# relay.net
KiCad netlist of a schematic drawn in Altium Designer
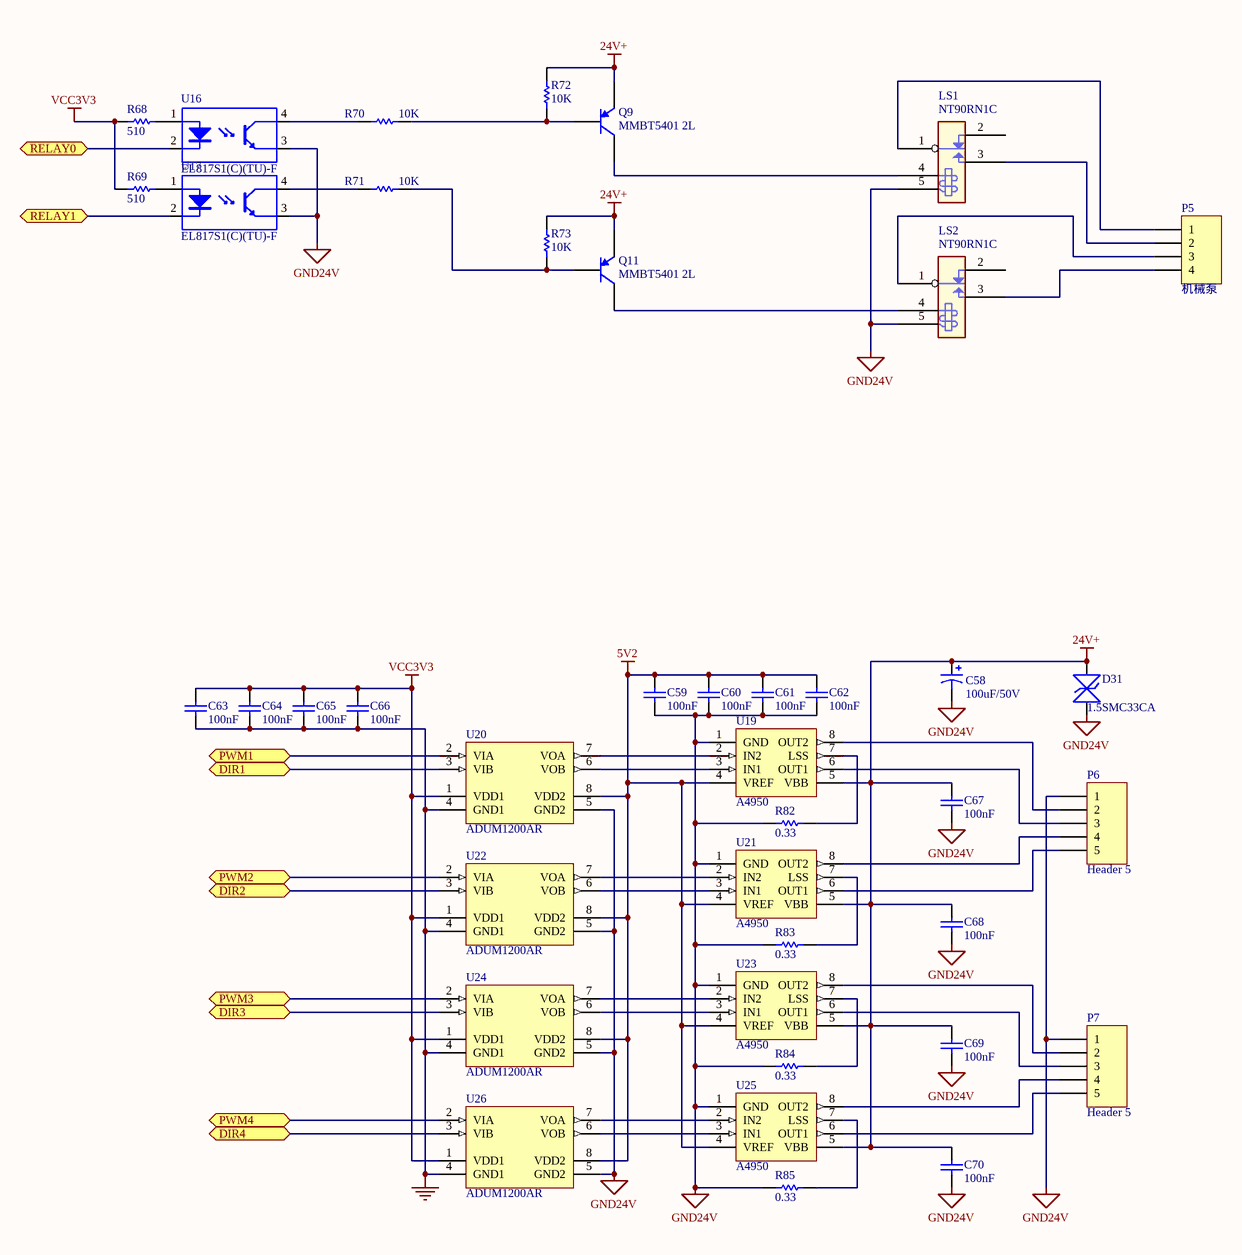
[diagram p0: relay.SchDoc]

(export (version "E")
  (design (tool "Eeschema 10.0.6"))
  (components
    (comp (ref "C58")
      (value "100uF/50V")
      (footprint "CD1.5/3.2")
      (description "Polarized Capacitor (Radial)")
      (fields (field (name "PUBLISHER") "Altium Limited"))
      (libsource (lib "Miscellaneous Devices") (part "Cap Pol1"))
    )
    (comp (ref "C59")
      (value "100nF")
      (footprint "0805_C")
      (description "贴片电容")
      (libsource (lib "Miscellaneous Devices LC") (part "0805 100nF(104) 10% 50V"))
    )
    (comp (ref "C60")
      (value "100nF")
      (footprint "0805_C")
      (description "贴片电容")
      (libsource (lib "Miscellaneous Devices LC") (part "0805 100nF(104) 10% 50V"))
    )
    (comp (ref "C61")
      (value "100nF")
      (footprint "0805_C")
      (description "贴片电容")
      (libsource (lib "Miscellaneous Devices LC") (part "0805 100nF(104) 10% 50V"))
    )
    (comp (ref "C62")
      (value "100nF")
      (footprint "0805_C")
      (description "贴片电容")
      (libsource (lib "Miscellaneous Devices LC") (part "0805 100nF(104) 10% 50V"))
    )
    (comp (ref "C63")
      (value "100nF")
      (footprint "0805_C")
      (description "贴片电容")
      (libsource (lib "Miscellaneous Devices LC") (part "0805 100nF(104) 10% 50V"))
    )
    (comp (ref "C64")
      (value "100nF")
      (footprint "0805_C")
      (description "贴片电容")
      (libsource (lib "Miscellaneous Devices LC") (part "0805 100nF(104) 10% 50V"))
    )
    (comp (ref "C65")
      (value "100nF")
      (footprint "0805_C")
      (description "贴片电容")
      (libsource (lib "Miscellaneous Devices LC") (part "0805 100nF(104) 10% 50V"))
    )
    (comp (ref "C66")
      (value "100nF")
      (footprint "0805_C")
      (description "贴片电容")
      (libsource (lib "Miscellaneous Devices LC") (part "0805 100nF(104) 10% 50V"))
    )
    (comp (ref "C67")
      (value "100nF")
      (footprint "0805_C")
      (description "贴片电容")
      (libsource (lib "Miscellaneous Devices LC") (part "0805 100nF(104) 10% 50V"))
    )
    (comp (ref "C68")
      (value "100nF")
      (footprint "0805_C")
      (description "贴片电容")
      (libsource (lib "Miscellaneous Devices LC") (part "0805 100nF(104) 10% 50V"))
    )
    (comp (ref "C69")
      (value "100nF")
      (footprint "0805_C")
      (description "贴片电容")
      (libsource (lib "Miscellaneous Devices LC") (part "0805 100nF(104) 10% 50V"))
    )
    (comp (ref "C70")
      (value "100nF")
      (footprint "0805_C")
      (description "贴片电容")
      (libsource (lib "Miscellaneous Devices LC") (part "0805 100nF(104) 10% 50V"))
    )
    (comp (ref "D31") (value "1.5SMC33CA") (footprint "SMC(DO-214AB)_S1") (libsource (lib "IC") (part "TVS")))
    (comp (ref "LS1") (value "NT90RN1C") (libsource (lib "Devices") (part "NT90RN1C")))
    (comp (ref "LS2") (value "NT90RN1C") (libsource (lib "Devices") (part "NT90RN1C")))
    (comp (ref "P5")
      (value "机械泵")
      (footprint "MSTBV 2.5/4-G-5.08")
      (description "Header, 4-Pin, Right Angle")
      (fields (field (name "PUBLISHER") "Altium Limited"))
      (libsource (lib "Miscellaneous Connectors") (part "Header 4H"))
    )
    (comp (ref "P6")
      (value "Header 5")
      (footprint "MC1.5/5-ST-3.81")
      (description "Header, 5-Pin")
      (fields (field (name "PUBLISHER") "Altium Limited"))
      (libsource (lib "Miscellaneous Connectors") (part "Header 5"))
    )
    (comp (ref "P7")
      (value "Header 5")
      (footprint "MC1.5/5-ST-3.81")
      (description "Header, 5-Pin")
      (fields (field (name "PUBLISHER") "Altium Limited"))
      (libsource (lib "Miscellaneous Connectors") (part "Header 5"))
    )
    (comp (ref "Q9")
      (value "MMBT5401 2L")
      (footprint "SOT-23(SOT-23-3)")
      (description "三极管")
      (libsource (lib "Miscellaneous Devices LC") (part "SOT-23 MMBT5401 2L"))
    )
    (comp (ref "Q11")
      (value "MMBT5401 2L")
      (footprint "SOT-23(SOT-23-3)")
      (description "三极管")
      (libsource (lib "Miscellaneous Devices LC") (part "SOT-23 MMBT5401 2L"))
    )
    (comp (ref "R68")
      (value "510")
      (footprint "0805_R")
      (description "Resistor")
      (fields (field (name "PUBLISHER") "Altium Limited"))
      (libsource (lib "Miscellaneous Devices") (part "Res1"))
    )
    (comp (ref "R69")
      (value "510")
      (footprint "0805_R")
      (description "Resistor")
      (fields (field (name "PUBLISHER") "Altium Limited"))
      (libsource (lib "Miscellaneous Devices") (part "Res1"))
    )
    (comp (ref "R70")
      (value "10K")
      (footprint "0805_R")
      (description "Resistor")
      (fields (field (name "PUBLISHER") "Altium Limited"))
      (libsource (lib "Miscellaneous Devices") (part "Res1"))
    )
    (comp (ref "R71")
      (value "10K")
      (footprint "0805_R")
      (description "Resistor")
      (fields (field (name "PUBLISHER") "Altium Limited"))
      (libsource (lib "Miscellaneous Devices") (part "Res1"))
    )
    (comp (ref "R72")
      (value "10K")
      (footprint "0805_R")
      (description "Resistor")
      (fields (field (name "PUBLISHER") "Altium Limited"))
      (libsource (lib "Miscellaneous Devices") (part "Res1"))
    )
    (comp (ref "R73")
      (value "10K")
      (footprint "0805_R")
      (description "Resistor")
      (fields (field (name "PUBLISHER") "Altium Limited"))
      (libsource (lib "Miscellaneous Devices") (part "Res1"))
    )
    (comp (ref "R82")
      (value "0.33")
      (footprint "R2512")
      (description "Resistor")
      (fields (field (name "PUBLISHER") "Altium Limited"))
      (libsource (lib "Miscellaneous Devices") (part "Res1"))
    )
    (comp (ref "R83")
      (value "0.33")
      (footprint "R2512")
      (description "Resistor")
      (fields (field (name "PUBLISHER") "Altium Limited"))
      (libsource (lib "Miscellaneous Devices") (part "Res1"))
    )
    (comp (ref "R84")
      (value "0.33")
      (footprint "R2512")
      (description "Resistor")
      (fields (field (name "PUBLISHER") "Altium Limited"))
      (libsource (lib "Miscellaneous Devices") (part "Res1"))
    )
    (comp (ref "R85")
      (value "0.33")
      (footprint "R2512")
      (description "Resistor")
      (fields (field (name "PUBLISHER") "Altium Limited"))
      (libsource (lib "Miscellaneous Devices") (part "Res1"))
    )
    (comp (ref "U16")
      (value "EL817S1(C)(TU)-F")
      (footprint "LC-SMD-4")
      (libsource (lib "IC") (part "TLP521"))
    )
    (comp (ref "U17")
      (value "EL817S1(C)(TU)-F")
      (footprint "LC-SMD-4")
      (libsource (lib "IC") (part "TLP521"))
    )
    (comp (ref "U19") (value "A4950") (footprint "LC-SOIC-8_EP_150mil") (libsource (lib "IC") (part "A4950")))
    (comp (ref "U20")
      (value "ADUM1200AR")
      (footprint "ADI-R-8_N")
      (fields (field (name "MANUFACTURER") "Analog Devices"))
      (libsource (lib "Analog Devices Interface and Isolation Digital Isolators") (part "ADUM1200AR"))
    )
    (comp (ref "U21") (value "A4950") (footprint "LC-SOIC-8_EP_150mil") (libsource (lib "IC") (part "A4950")))
    (comp (ref "U22")
      (value "ADUM1200AR")
      (footprint "ADI-R-8_N")
      (fields (field (name "MANUFACTURER") "Analog Devices"))
      (libsource (lib "Analog Devices Interface and Isolation Digital Isolators") (part "ADUM1200AR"))
    )
    (comp (ref "U23") (value "A4950") (footprint "LC-SOIC-8_EP_150mil") (libsource (lib "IC") (part "A4950")))
    (comp (ref "U24")
      (value "ADUM1200AR")
      (footprint "ADI-R-8_N")
      (fields (field (name "MANUFACTURER") "Analog Devices"))
      (libsource (lib "Analog Devices Interface and Isolation Digital Isolators") (part "ADUM1200AR"))
    )
    (comp (ref "U25") (value "A4950") (footprint "LC-SOIC-8_EP_150mil") (libsource (lib "IC") (part "A4950")))
    (comp (ref "U26")
      (value "ADUM1200AR")
      (footprint "ADI-R-8_N")
      (fields (field (name "MANUFACTURER") "Analog Devices"))
      (libsource (lib "Analog Devices Interface and Isolation Digital Isolators") (part "ADUM1200AR"))
    )
  )
  (nets
    (net (code "1") (name "/DIR1") (class "Default")
      (node (ref "U20") (pin "3") (pinfunction "VIB_3") (pintype "input"))
    )
    (net (code "2") (name "/DIR2") (class "Default")
      (node (ref "U22") (pin "3") (pinfunction "VIB_3") (pintype "input"))
    )
    (net (code "3") (name "/DIR3") (class "Default")
      (node (ref "U24") (pin "3") (pinfunction "VIB_3") (pintype "input"))
    )
    (net (code "4") (name "/DIR4") (class "Default")
      (node (ref "U26") (pin "3") (pinfunction "VIB_3") (pintype "input"))
    )
    (net (code "5") (name "/PWM1") (class "Default")
      (node (ref "U20") (pin "2") (pinfunction "VIA_2") (pintype "input"))
    )
    (net (code "6") (name "/PWM2") (class "Default")
      (node (ref "U22") (pin "2") (pinfunction "VIA_2") (pintype "input"))
    )
    (net (code "7") (name "/PWM3") (class "Default")
      (node (ref "U24") (pin "2") (pinfunction "VIA_2") (pintype "input"))
    )
    (net (code "8") (name "/PWM4") (class "Default")
      (node (ref "U26") (pin "2") (pinfunction "VIA_2") (pintype "input"))
    )
    (net (code "9") (name "/RELAY0") (class "Default")
      (node (ref "U16") (pin "2") (pinfunction "K_2") (pintype "passive"))
    )
    (net (code "10") (name "/RELAY1") (class "Default")
      (node (ref "U17") (pin "2") (pinfunction "K_2") (pintype "passive"))
    )
    (net (code "11") (name "5V2") (class "Default")
      (node (ref "C59") (pin "2") (pinfunction "2_2") (pintype "passive"))
      (node (ref "C60") (pin "2") (pinfunction "2_2") (pintype "passive"))
      (node (ref "C61") (pin "2") (pinfunction "2_2") (pintype "passive"))
      (node (ref "C62") (pin "2") (pinfunction "2_2") (pintype "passive"))
      (node (ref "U19") (pin "4") (pinfunction "VREF_4") (pintype "power_in"))
      (node (ref "U20") (pin "8") (pinfunction "VDD2_8") (pintype "power_in"))
      (node (ref "U21") (pin "4") (pinfunction "VREF_4") (pintype "power_in"))
      (node (ref "U22") (pin "8") (pinfunction "VDD2_8") (pintype "power_in"))
      (node (ref "U23") (pin "4") (pinfunction "VREF_4") (pintype "power_in"))
      (node (ref "U24") (pin "8") (pinfunction "VDD2_8") (pintype "power_in"))
      (node (ref "U25") (pin "4") (pinfunction "VREF_4") (pintype "power_in"))
      (node (ref "U26") (pin "8") (pinfunction "VDD2_8") (pintype "power_in"))
    )
    (net (code "12") (name "24V+") (class "Default")
      (node (ref "C58") (pin "1") (pinfunction "1_1") (pintype "passive"))
      (node (ref "C67") (pin "2") (pinfunction "2_2") (pintype "passive"))
      (node (ref "C68") (pin "2") (pinfunction "2_2") (pintype "passive"))
      (node (ref "C69") (pin "2") (pinfunction "2_2") (pintype "passive"))
      (node (ref "C70") (pin "2") (pinfunction "2_2") (pintype "passive"))
      (node (ref "D31") (pin "2") (pinfunction "2_2") (pintype "passive"))
      (node (ref "Q11") (pin "2") (pinfunction "E_2") (pintype "passive"))
      (node (ref "Q9") (pin "2") (pinfunction "E_2") (pintype "passive"))
      (node (ref "R72") (pin "2") (pinfunction "2_2") (pintype "passive"))
      (node (ref "R73") (pin "2") (pinfunction "2_2") (pintype "passive"))
      (node (ref "U19") (pin "5") (pinfunction "VBB_5") (pintype "power_in"))
      (node (ref "U21") (pin "5") (pinfunction "VBB_5") (pintype "power_in"))
      (node (ref "U23") (pin "5") (pinfunction "VBB_5") (pintype "power_in"))
      (node (ref "U25") (pin "5") (pinfunction "VBB_5") (pintype "power_in"))
    )
    (net (code "13") (name "GND") (class "Default")
      (node (ref "C63") (pin "1") (pinfunction "1_1") (pintype "passive"))
      (node (ref "C64") (pin "1") (pinfunction "1_1") (pintype "passive"))
      (node (ref "C65") (pin "1") (pinfunction "1_1") (pintype "passive"))
      (node (ref "C66") (pin "1") (pinfunction "1_1") (pintype "passive"))
      (node (ref "U20") (pin "4") (pinfunction "GND1_4") (pintype "power_in"))
      (node (ref "U22") (pin "4") (pinfunction "GND1_4") (pintype "power_in"))
      (node (ref "U24") (pin "4") (pinfunction "GND1_4") (pintype "power_in"))
      (node (ref "U26") (pin "4") (pinfunction "GND1_4") (pintype "power_in"))
    )
    (net (code "14") (name "GND24V") (class "Default")
      (node (ref "C58") (pin "2") (pinfunction "2_2") (pintype "passive"))
      (node (ref "C59") (pin "1") (pinfunction "1_1") (pintype "passive"))
      (node (ref "C60") (pin "1") (pinfunction "1_1") (pintype "passive"))
      (node (ref "C61") (pin "1") (pinfunction "1_1") (pintype "passive"))
      (node (ref "C62") (pin "1") (pinfunction "1_1") (pintype "passive"))
      (node (ref "C67") (pin "1") (pinfunction "1_1") (pintype "passive"))
      (node (ref "C68") (pin "1") (pinfunction "1_1") (pintype "passive"))
      (node (ref "C69") (pin "1") (pinfunction "1_1") (pintype "passive"))
      (node (ref "C70") (pin "1") (pinfunction "1_1") (pintype "passive"))
      (node (ref "D31") (pin "1") (pinfunction "1_1") (pintype "passive"))
      (node (ref "LS1") (pin "5") (pinfunction "COIL2_5") (pintype "passive"))
      (node (ref "LS2") (pin "5") (pinfunction "COIL2_5") (pintype "passive"))
      (node (ref "P6") (pin "1") (pinfunction "1_1") (pintype "passive"))
      (node (ref "P7") (pin "1") (pinfunction "1_1") (pintype "passive"))
      (node (ref "R82") (pin "2") (pinfunction "2_2") (pintype "passive"))
      (node (ref "R83") (pin "2") (pinfunction "2_2") (pintype "passive"))
      (node (ref "R84") (pin "2") (pinfunction "2_2") (pintype "passive"))
      (node (ref "R85") (pin "2") (pinfunction "2_2") (pintype "passive"))
      (node (ref "U16") (pin "3") (pinfunction "E_3") (pintype "passive"))
      (node (ref "U17") (pin "3") (pinfunction "E_3") (pintype "passive"))
      (node (ref "U19") (pin "1") (pinfunction "GND_1") (pintype "power_in"))
      (node (ref "U20") (pin "5") (pinfunction "GND2_5") (pintype "power_in"))
      (node (ref "U21") (pin "1") (pinfunction "GND_1") (pintype "power_in"))
      (node (ref "U22") (pin "5") (pinfunction "GND2_5") (pintype "power_in"))
      (node (ref "U23") (pin "1") (pinfunction "GND_1") (pintype "power_in"))
      (node (ref "U24") (pin "5") (pinfunction "GND2_5") (pintype "power_in"))
      (node (ref "U25") (pin "1") (pinfunction "GND_1") (pintype "power_in"))
      (node (ref "U26") (pin "5") (pinfunction "GND2_5") (pintype "power_in"))
    )
    (net (code "15") (name "Net-(LS1-COIL1)") (class "Default")
      (node (ref "LS1") (pin "4") (pinfunction "COIL1_4") (pintype "passive"))
      (node (ref "Q9") (pin "3") (pinfunction "C_3") (pintype "passive"))
    )
    (net (code "16") (name "Net-(LS1-COMMON)") (class "Default")
      (node (ref "LS1") (pin "1") (pinfunction "COMMON_1") (pintype "passive"))
      (node (ref "P5") (pin "1") (pinfunction "1_1") (pintype "passive"))
    )
    (net (code "17") (name "Net-(LS1-NO)") (class "Default")
      (node (ref "LS1") (pin "3") (pinfunction "NO_3") (pintype "passive"))
      (node (ref "P5") (pin "2") (pinfunction "2_2") (pintype "passive"))
    )
    (net (code "18") (name "Net-(LS2-COIL1)") (class "Default")
      (node (ref "LS2") (pin "4") (pinfunction "COIL1_4") (pintype "passive"))
      (node (ref "Q11") (pin "3") (pinfunction "C_3") (pintype "passive"))
    )
    (net (code "19") (name "Net-(LS2-COMMON)") (class "Default")
      (node (ref "LS2") (pin "1") (pinfunction "COMMON_1") (pintype "passive"))
      (node (ref "P5") (pin "3") (pinfunction "3_3") (pintype "passive"))
    )
    (net (code "20") (name "Net-(LS2-NO)") (class "Default")
      (node (ref "LS2") (pin "3") (pinfunction "NO_3") (pintype "passive"))
      (node (ref "P5") (pin "4") (pinfunction "4_4") (pintype "passive"))
    )
    (net (code "21") (name "Net-(Q9-B)") (class "Default")
      (node (ref "Q9") (pin "1") (pinfunction "B_1") (pintype "passive"))
      (node (ref "R70") (pin "2") (pinfunction "2_2") (pintype "passive"))
      (node (ref "R72") (pin "1") (pinfunction "1_1") (pintype "passive"))
    )
    (net (code "22") (name "Net-(Q11-B)") (class "Default")
      (node (ref "Q11") (pin "1") (pinfunction "B_1") (pintype "passive"))
      (node (ref "R71") (pin "2") (pinfunction "2_2") (pintype "passive"))
      (node (ref "R73") (pin "1") (pinfunction "1_1") (pintype "passive"))
    )
    (net (code "23") (name "Net-(U16-A)") (class "Default")
      (node (ref "R68") (pin "1") (pinfunction "1_1") (pintype "passive"))
      (node (ref "U16") (pin "1") (pinfunction "A_1") (pintype "passive"))
    )
    (net (code "24") (name "Net-(U16-C)") (class "Default")
      (node (ref "R70") (pin "1") (pinfunction "1_1") (pintype "passive"))
      (node (ref "U16") (pin "4") (pinfunction "C_4") (pintype "passive"))
    )
    (net (code "25") (name "Net-(U17-A)") (class "Default")
      (node (ref "R69") (pin "1") (pinfunction "1_1") (pintype "passive"))
      (node (ref "U17") (pin "1") (pinfunction "A_1") (pintype "passive"))
    )
    (net (code "26") (name "Net-(U17-C)") (class "Default")
      (node (ref "R71") (pin "1") (pinfunction "1_1") (pintype "passive"))
      (node (ref "U17") (pin "4") (pinfunction "C_4") (pintype "passive"))
    )
    (net (code "27") (name "Net-(U19-IN1)") (class "Default")
      (node (ref "U19") (pin "3") (pinfunction "IN1_3") (pintype "input"))
      (node (ref "U20") (pin "6") (pinfunction "VOB_6") (pintype "output"))
    )
    (net (code "28") (name "Net-(U19-IN2)") (class "Default")
      (node (ref "U19") (pin "2") (pinfunction "IN2_2") (pintype "input"))
      (node (ref "U20") (pin "7") (pinfunction "VOA_7") (pintype "output"))
    )
    (net (code "29") (name "Net-(U19-LSS)") (class "Default")
      (node (ref "R82") (pin "1") (pinfunction "1_1") (pintype "passive"))
      (node (ref "U19") (pin "7") (pinfunction "LSS_7") (pintype "output"))
    )
    (net (code "30") (name "Net-(U19-OUT1)") (class "Default")
      (node (ref "P6") (pin "3") (pinfunction "3_3") (pintype "passive"))
      (node (ref "U19") (pin "6") (pinfunction "OUT1_6") (pintype "output"))
    )
    (net (code "31") (name "Net-(U19-OUT2)") (class "Default")
      (node (ref "P6") (pin "2") (pinfunction "2_2") (pintype "passive"))
      (node (ref "U19") (pin "8") (pinfunction "OUT2_8") (pintype "output"))
    )
    (net (code "32") (name "Net-(U21-IN1)") (class "Default")
      (node (ref "U21") (pin "3") (pinfunction "IN1_3") (pintype "input"))
      (node (ref "U22") (pin "6") (pinfunction "VOB_6") (pintype "output"))
    )
    (net (code "33") (name "Net-(U21-IN2)") (class "Default")
      (node (ref "U21") (pin "2") (pinfunction "IN2_2") (pintype "input"))
      (node (ref "U22") (pin "7") (pinfunction "VOA_7") (pintype "output"))
    )
    (net (code "34") (name "Net-(U21-LSS)") (class "Default")
      (node (ref "R83") (pin "1") (pinfunction "1_1") (pintype "passive"))
      (node (ref "U21") (pin "7") (pinfunction "LSS_7") (pintype "output"))
    )
    (net (code "35") (name "Net-(U21-OUT1)") (class "Default")
      (node (ref "P6") (pin "5") (pinfunction "5_5") (pintype "passive"))
      (node (ref "U21") (pin "6") (pinfunction "OUT1_6") (pintype "output"))
    )
    (net (code "36") (name "Net-(U21-OUT2)") (class "Default")
      (node (ref "P6") (pin "4") (pinfunction "4_4") (pintype "passive"))
      (node (ref "U21") (pin "8") (pinfunction "OUT2_8") (pintype "output"))
    )
    (net (code "37") (name "Net-(U23-IN1)") (class "Default")
      (node (ref "U23") (pin "3") (pinfunction "IN1_3") (pintype "input"))
      (node (ref "U24") (pin "6") (pinfunction "VOB_6") (pintype "output"))
    )
    (net (code "38") (name "Net-(U23-IN2)") (class "Default")
      (node (ref "U23") (pin "2") (pinfunction "IN2_2") (pintype "input"))
      (node (ref "U24") (pin "7") (pinfunction "VOA_7") (pintype "output"))
    )
    (net (code "39") (name "Net-(U23-LSS)") (class "Default")
      (node (ref "R84") (pin "1") (pinfunction "1_1") (pintype "passive"))
      (node (ref "U23") (pin "7") (pinfunction "LSS_7") (pintype "output"))
    )
    (net (code "40") (name "Net-(U23-OUT1)") (class "Default")
      (node (ref "P7") (pin "3") (pinfunction "3_3") (pintype "passive"))
      (node (ref "U23") (pin "6") (pinfunction "OUT1_6") (pintype "output"))
    )
    (net (code "41") (name "Net-(U23-OUT2)") (class "Default")
      (node (ref "P7") (pin "2") (pinfunction "2_2") (pintype "passive"))
      (node (ref "U23") (pin "8") (pinfunction "OUT2_8") (pintype "output"))
    )
    (net (code "42") (name "Net-(U25-IN1)") (class "Default")
      (node (ref "U25") (pin "3") (pinfunction "IN1_3") (pintype "input"))
      (node (ref "U26") (pin "6") (pinfunction "VOB_6") (pintype "output"))
    )
    (net (code "43") (name "Net-(U25-IN2)") (class "Default")
      (node (ref "U25") (pin "2") (pinfunction "IN2_2") (pintype "input"))
      (node (ref "U26") (pin "7") (pinfunction "VOA_7") (pintype "output"))
    )
    (net (code "44") (name "Net-(U25-LSS)") (class "Default")
      (node (ref "R85") (pin "1") (pinfunction "1_1") (pintype "passive"))
      (node (ref "U25") (pin "7") (pinfunction "LSS_7") (pintype "output"))
    )
    (net (code "45") (name "Net-(U25-OUT1)") (class "Default")
      (node (ref "P7") (pin "5") (pinfunction "5_5") (pintype "passive"))
      (node (ref "U25") (pin "6") (pinfunction "OUT1_6") (pintype "output"))
    )
    (net (code "46") (name "Net-(U25-OUT2)") (class "Default")
      (node (ref "P7") (pin "4") (pinfunction "4_4") (pintype "passive"))
      (node (ref "U25") (pin "8") (pinfunction "OUT2_8") (pintype "output"))
    )
    (net (code "47") (name "VCC3V3") (class "Default")
      (node (ref "C63") (pin "2") (pinfunction "2_2") (pintype "passive"))
      (node (ref "C64") (pin "2") (pinfunction "2_2") (pintype "passive"))
      (node (ref "C65") (pin "2") (pinfunction "2_2") (pintype "passive"))
      (node (ref "C66") (pin "2") (pinfunction "2_2") (pintype "passive"))
      (node (ref "R68") (pin "2") (pinfunction "2_2") (pintype "passive"))
      (node (ref "R69") (pin "2") (pinfunction "2_2") (pintype "passive"))
      (node (ref "U20") (pin "1") (pinfunction "VDD1_1") (pintype "power_in"))
      (node (ref "U22") (pin "1") (pinfunction "VDD1_1") (pintype "power_in"))
      (node (ref "U24") (pin "1") (pinfunction "VDD1_1") (pintype "power_in"))
      (node (ref "U26") (pin "1") (pinfunction "VDD1_1") (pintype "power_in"))
    )
    (net (code "48") (name "unconnected-(LS1-NC-Pad2)") (class "Default")
      (node (ref "LS1") (pin "2") (pinfunction "NC_2") (pintype "passive"))
    )
    (net (code "49") (name "unconnected-(LS2-NC-Pad2)") (class "Default")
      (node (ref "LS2") (pin "2") (pinfunction "NC_2") (pintype "passive"))
    )
  )
)
